# LPCB221_-_MLP.net
KiCad netlist of a schematic drawn in Altium Designer
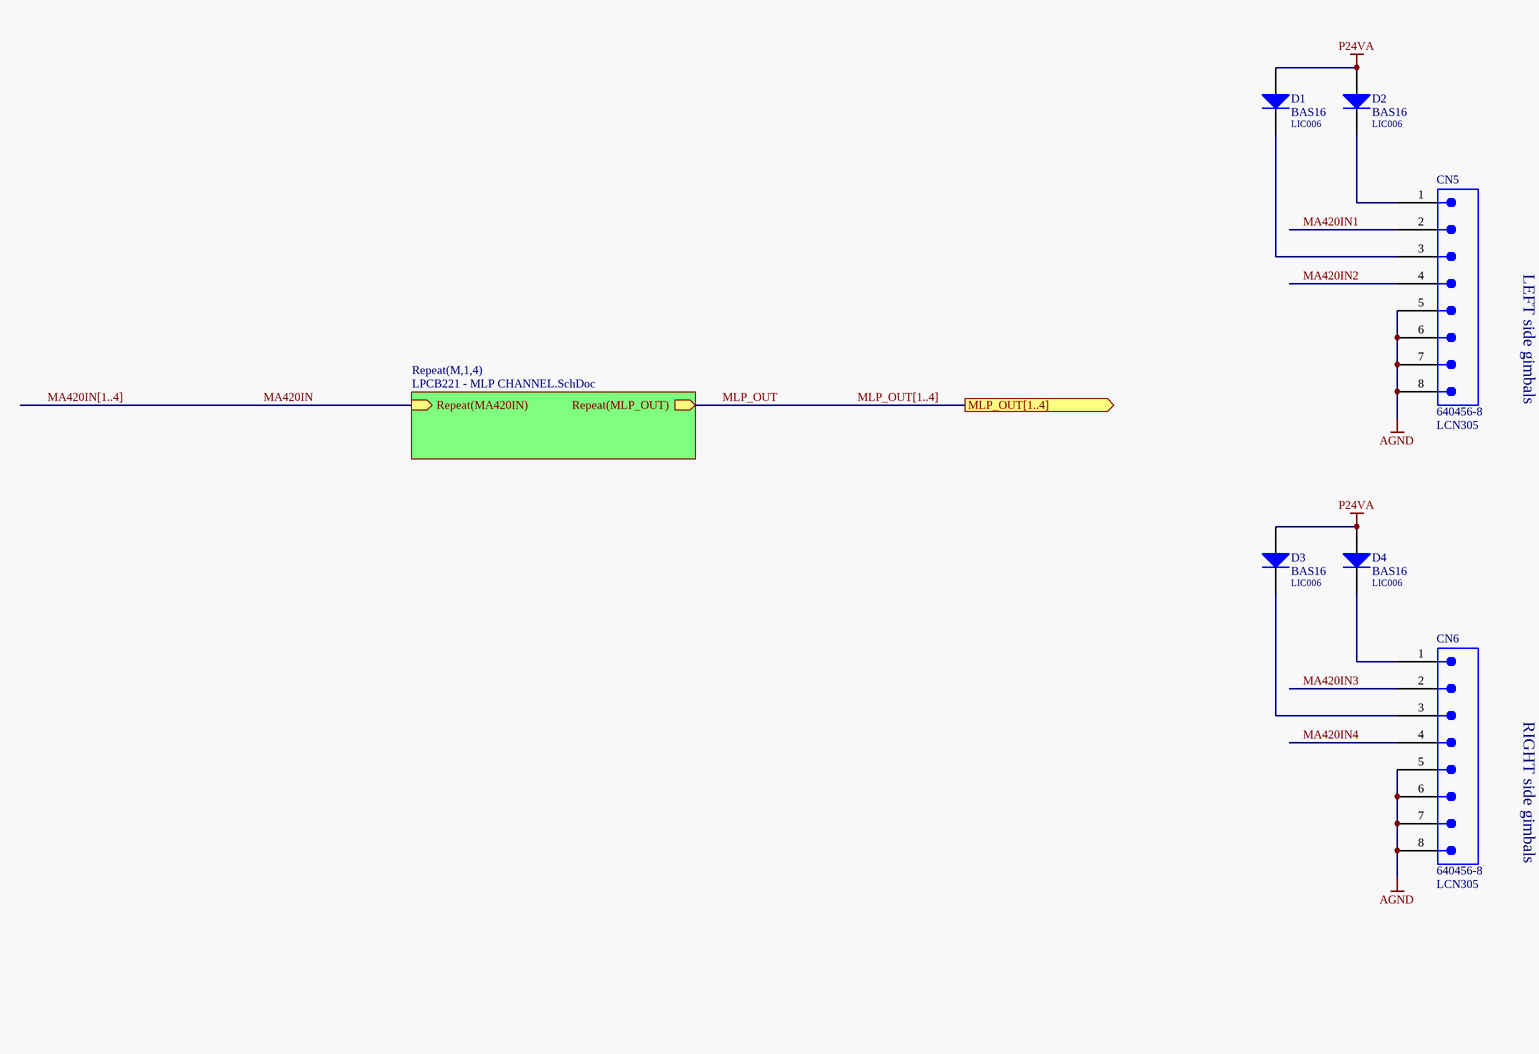
[diagram p0: LPCB221 - MLP.SchDoc]

(export (version "E")
  (design (tool "Eeschema 10.0.6"))
  (components
    (comp (ref "CN5")
      (value "640456-8")
      (footprint "640456-8")
      (description "Connector, Male Header, 8 Way")
      (fields (field (name "LDL_NUMBER") "LCN305"))
      (libsource (lib "LDL_Connectors") (part "640456-8"))
    )
    (comp (ref "CN6")
      (value "640456-8")
      (footprint "640456-8")
      (description "Connector, Male Header, 8 Way")
      (fields (field (name "LDL_NUMBER") "LCN305"))
      (libsource (lib "LDL_Connectors") (part "640456-8"))
    )
    (comp (ref "D1")
      (value "BAS16")
      (footprint "LFP021__SOT23")
      (description "Diode, Small Signal, 0.2A, 85V, SMD SOT-23 [LIC006]")
      (fields (field (name "LDL_NUMBER") "LIC006"))
      (libsource (lib "LDL_Semiconductors") (part "BAS16"))
    )
    (comp (ref "D2")
      (value "BAS16")
      (footprint "LFP021__SOT23")
      (description "Diode, Small Signal, 0.2A, 85V, SMD SOT-23 [LIC006]")
      (fields (field (name "LDL_NUMBER") "LIC006"))
      (libsource (lib "LDL_Semiconductors") (part "BAS16"))
    )
    (comp (ref "D3")
      (value "BAS16")
      (footprint "LFP021__SOT23")
      (description "Diode, Small Signal, 0.2A, 85V, SMD SOT-23 [LIC006]")
      (fields (field (name "LDL_NUMBER") "LIC006"))
      (libsource (lib "LDL_Semiconductors") (part "BAS16"))
    )
    (comp (ref "D4")
      (value "BAS16")
      (footprint "LFP021__SOT23")
      (description "Diode, Small Signal, 0.2A, 85V, SMD SOT-23 [LIC006]")
      (fields (field (name "LDL_NUMBER") "LIC006"))
      (libsource (lib "LDL_Semiconductors") (part "BAS16"))
    )
  )
  (nets
    (net (code "6") (name "/MA420IN1") (class "Default")
      (node (ref "CN5") (pin "2") (pinfunction "2_2") (pintype "passive"))
    )
    (net (code "7") (name "/MA420IN2") (class "Default")
      (node (ref "CN5") (pin "4") (pinfunction "4_4") (pintype "passive"))
    )
    (net (code "8") (name "/MA420IN3") (class "Default")
      (node (ref "CN6") (pin "2") (pinfunction "2_2") (pintype "passive"))
    )
    (net (code "9") (name "/MA420IN4") (class "Default")
      (node (ref "CN6") (pin "4") (pinfunction "4_4") (pintype "passive"))
    )
    (net (code "13") (name "AGND") (class "Default")
      (node (ref "CN5") (pin "5") (pinfunction "5_5") (pintype "passive"))
      (node (ref "CN5") (pin "6") (pinfunction "6_6") (pintype "passive"))
      (node (ref "CN5") (pin "7") (pinfunction "7_7") (pintype "passive"))
      (node (ref "CN5") (pin "8") (pinfunction "8_8") (pintype "passive"))
      (node (ref "CN6") (pin "5") (pinfunction "5_5") (pintype "passive"))
      (node (ref "CN6") (pin "6") (pinfunction "6_6") (pintype "passive"))
      (node (ref "CN6") (pin "7") (pinfunction "7_7") (pintype "passive"))
      (node (ref "CN6") (pin "8") (pinfunction "8_8") (pintype "passive"))
    )
    (net (code "14") (name "Net-(D1-K)") (class "Default")
      (node (ref "CN5") (pin "3") (pinfunction "3_3") (pintype "passive"))
      (node (ref "D1") (pin "3") (pinfunction "K_3") (pintype "passive"))
    )
    (net (code "15") (name "Net-(D2-K)") (class "Default")
      (node (ref "CN5") (pin "1") (pinfunction "1_1") (pintype "passive"))
      (node (ref "D2") (pin "3") (pinfunction "K_3") (pintype "passive"))
    )
    (net (code "16") (name "Net-(D3-K)") (class "Default")
      (node (ref "CN6") (pin "3") (pinfunction "3_3") (pintype "passive"))
      (node (ref "D3") (pin "3") (pinfunction "K_3") (pintype "passive"))
    )
    (net (code "17") (name "Net-(D4-K)") (class "Default")
      (node (ref "CN6") (pin "1") (pinfunction "1_1") (pintype "passive"))
      (node (ref "D4") (pin "3") (pinfunction "K_3") (pintype "passive"))
    )
    (net (code "18") (name "P24VA") (class "Default")
      (node (ref "D1") (pin "1") (pinfunction "A_1") (pintype "passive"))
      (node (ref "D2") (pin "1") (pinfunction "A_1") (pintype "passive"))
      (node (ref "D3") (pin "1") (pinfunction "A_1") (pintype "passive"))
      (node (ref "D4") (pin "1") (pinfunction "A_1") (pintype "passive"))
    )
  )
)
